# MicroMod-Teensy-Lockable.net
KiCad netlist of a schematic drawn in EAGLE
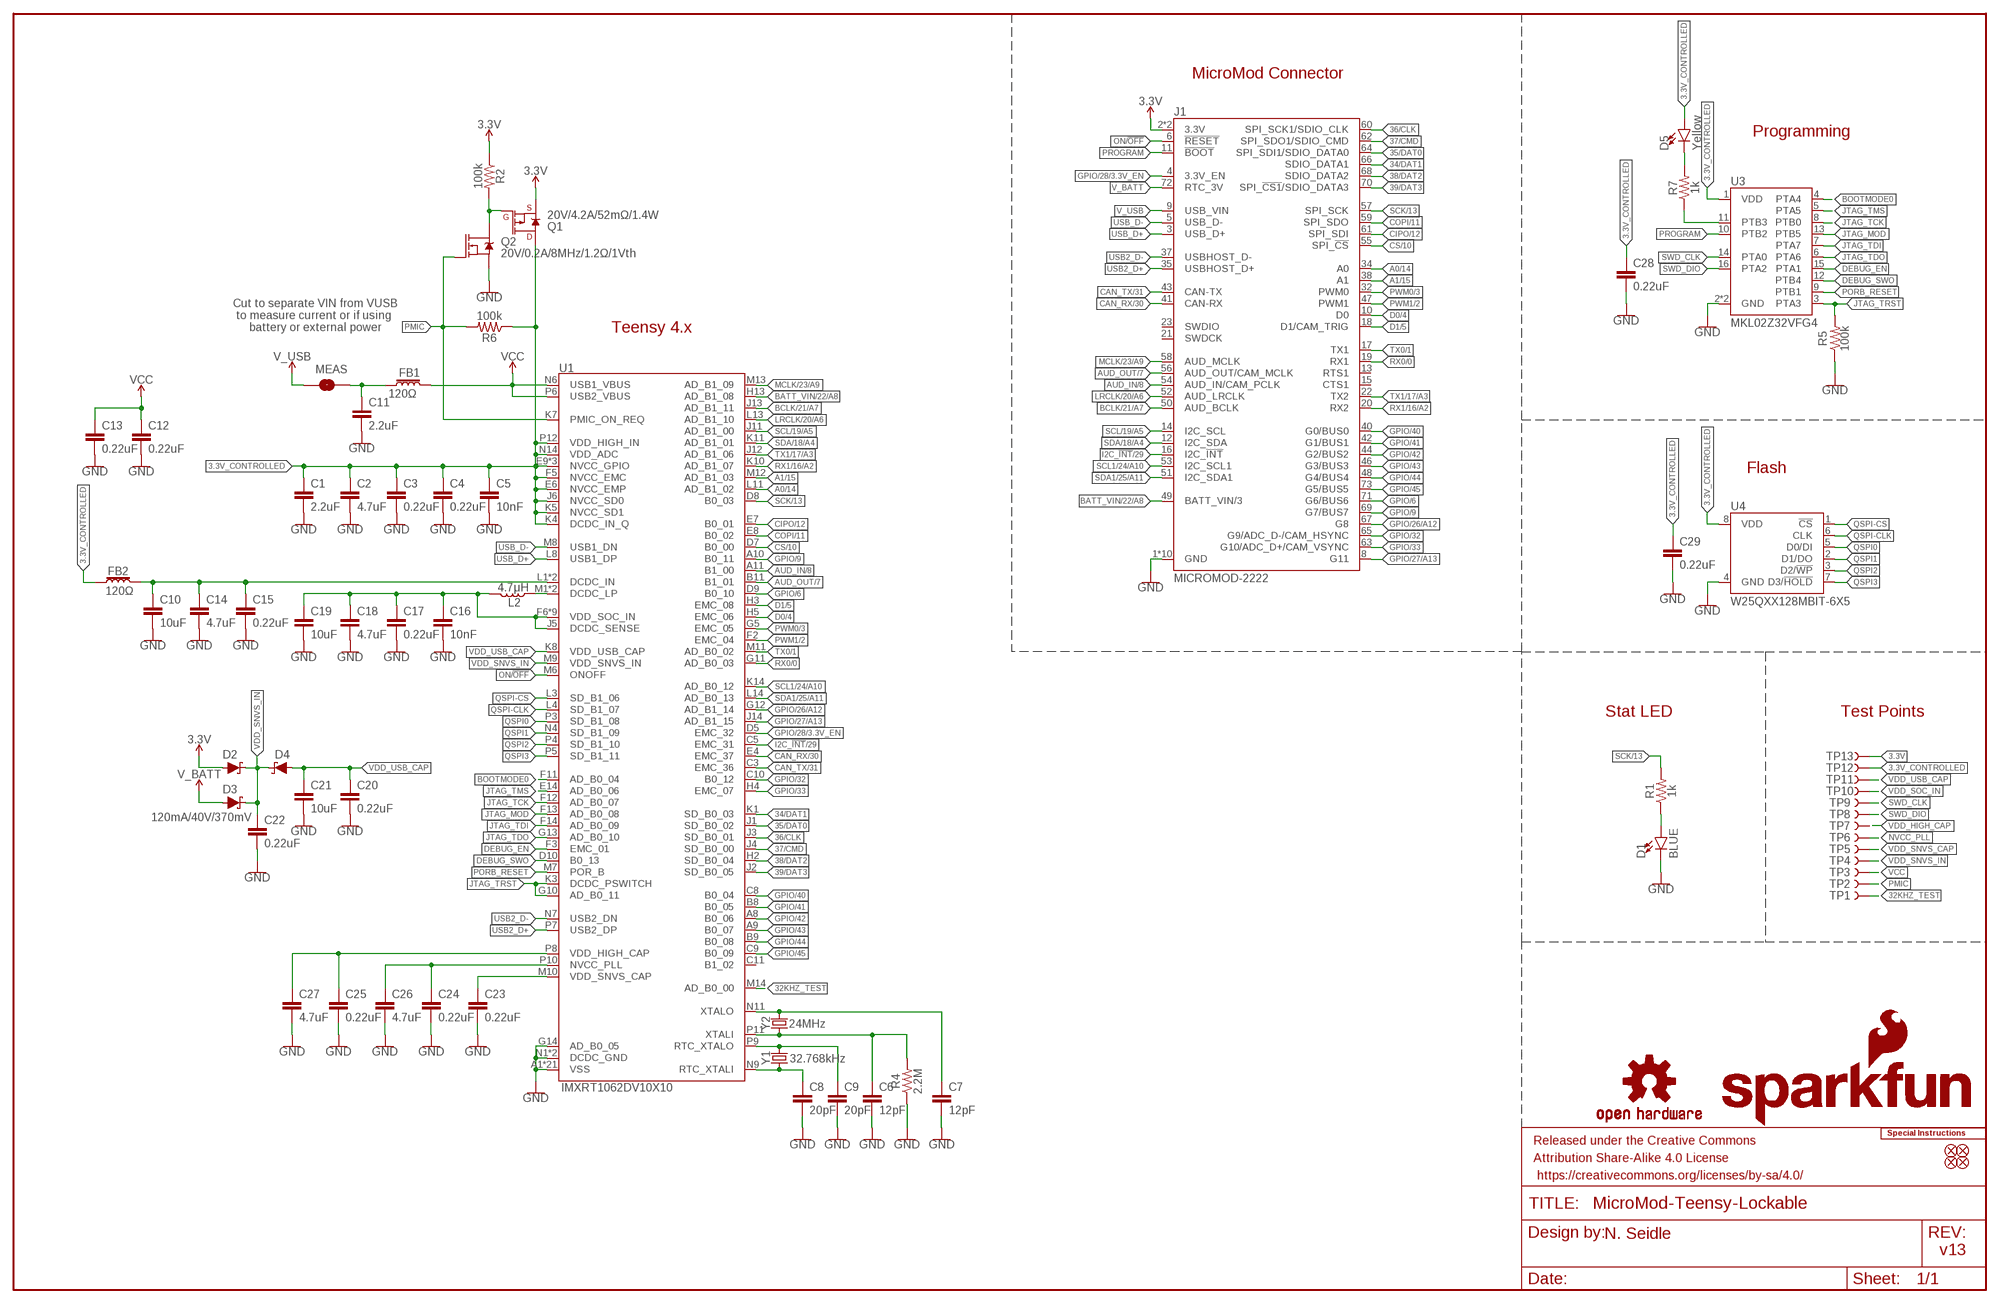
[diagram p0: schematic, sheet 1]

(export (version "E")
  (design (tool "Eeschema 10.0.6"))
  (components
    (comp (ref "C1")
      (value "2.2uF")
      (footprint "eagle-import:0402-TIGHT")
      (libsource (lib "eagle-import") (part "2.2UF-0402_TIGHT-10V-10%-X5R"))
    )
    (comp (ref "C2")
      (value "4.7uF")
      (footprint "eagle-import:0402-TIGHT")
      (libsource (lib "eagle-import") (part "4.7UF-0402_TIGHT-6.3V-20%-X5R"))
    )
    (comp (ref "C3")
      (value "0.22uF")
      (footprint "eagle-import:0402-TIGHT")
      (libsource (lib "eagle-import") (part "0.22UF-0402T-10V-10%"))
    )
    (comp (ref "C4")
      (value "0.22uF")
      (footprint "eagle-import:0402-TIGHT")
      (libsource (lib "eagle-import") (part "0.22UF-0402T-10V-10%"))
    )
    (comp (ref "C5")
      (value "10nF")
      (footprint "eagle-import:0402-TIGHT")
      (libsource (lib "eagle-import") (part "10NF-0402T-25V-10%"))
    )
    (comp (ref "C6")
      (value "12pF")
      (footprint "eagle-import:0402-TIGHT")
      (libsource (lib "eagle-import") (part "12PF-0402T-50V-5%"))
    )
    (comp (ref "C7")
      (value "12pF")
      (footprint "eagle-import:0402-TIGHT")
      (libsource (lib "eagle-import") (part "12PF-0402T-50V-5%"))
    )
    (comp (ref "C8")
      (value "20pF")
      (footprint "eagle-import:0402-TIGHT")
      (libsource (lib "eagle-import") (part "20PF-0402T-50V-5%"))
    )
    (comp (ref "C9")
      (value "20pF")
      (footprint "eagle-import:0402-TIGHT")
      (libsource (lib "eagle-import") (part "20PF-0402T-50V-5%"))
    )
    (comp (ref "C10")
      (value "10uF")
      (footprint "eagle-import:0402-TIGHT")
      (libsource (lib "eagle-import") (part "10UF-0402T-6.3V-20%"))
    )
    (comp (ref "C11")
      (value "2.2uF")
      (footprint "eagle-import:0402-TIGHT")
      (libsource (lib "eagle-import") (part "2.2UF-0402_TIGHT-10V-10%-X5R"))
    )
    (comp (ref "C12")
      (value "0.22uF")
      (footprint "eagle-import:0402-TIGHT")
      (libsource (lib "eagle-import") (part "0.22UF-0402T-10V-10%"))
    )
    (comp (ref "C13")
      (value "0.22uF")
      (footprint "eagle-import:0402-TIGHT")
      (libsource (lib "eagle-import") (part "0.22UF-0402T-10V-10%"))
    )
    (comp (ref "C14")
      (value "4.7uF")
      (footprint "eagle-import:0402-TIGHT")
      (libsource (lib "eagle-import") (part "4.7UF-0402_TIGHT-6.3V-20%-X5R"))
    )
    (comp (ref "C15")
      (value "0.22uF")
      (footprint "eagle-import:0402-TIGHT")
      (libsource (lib "eagle-import") (part "0.22UF-0402T-10V-10%"))
    )
    (comp (ref "C16")
      (value "10nF")
      (footprint "eagle-import:0402-TIGHT")
      (libsource (lib "eagle-import") (part "10NF-0402T-25V-10%"))
    )
    (comp (ref "C17")
      (value "0.22uF")
      (footprint "eagle-import:0402-TIGHT")
      (libsource (lib "eagle-import") (part "0.22UF-0402T-10V-10%"))
    )
    (comp (ref "C18")
      (value "4.7uF")
      (footprint "eagle-import:0402-TIGHT")
      (libsource (lib "eagle-import") (part "4.7UF-0402_TIGHT-6.3V-20%-X5R"))
    )
    (comp (ref "C19")
      (value "10uF")
      (footprint "eagle-import:0402-TIGHT")
      (libsource (lib "eagle-import") (part "10UF-0402T-6.3V-20%"))
    )
    (comp (ref "C20")
      (value "0.22uF")
      (footprint "eagle-import:0402-TIGHT")
      (libsource (lib "eagle-import") (part "0.22UF-0402T-10V-10%"))
    )
    (comp (ref "C21")
      (value "10uF")
      (footprint "eagle-import:0402-TIGHT")
      (libsource (lib "eagle-import") (part "10UF-0402T-6.3V-20%"))
    )
    (comp (ref "C22")
      (value "0.22uF")
      (footprint "eagle-import:0402-TIGHT")
      (libsource (lib "eagle-import") (part "0.22UF-0402T-10V-10%"))
    )
    (comp (ref "C23")
      (value "0.22uF")
      (footprint "eagle-import:0402-TIGHT")
      (libsource (lib "eagle-import") (part "0.22UF-0402T-10V-10%"))
    )
    (comp (ref "C24")
      (value "0.22uF")
      (footprint "eagle-import:0402-TIGHT")
      (libsource (lib "eagle-import") (part "0.22UF-0402T-10V-10%"))
    )
    (comp (ref "C25")
      (value "0.22uF")
      (footprint "eagle-import:0402-TIGHT")
      (libsource (lib "eagle-import") (part "0.22UF-0402T-10V-10%"))
    )
    (comp (ref "C26")
      (value "4.7uF")
      (footprint "eagle-import:0402-TIGHT")
      (libsource (lib "eagle-import") (part "4.7UF-0402_TIGHT-6.3V-20%-X5R"))
    )
    (comp (ref "C27")
      (value "4.7uF")
      (footprint "eagle-import:0402-TIGHT")
      (libsource (lib "eagle-import") (part "4.7UF-0402_TIGHT-6.3V-20%-X5R"))
    )
    (comp (ref "C28")
      (value "0.22uF")
      (footprint "eagle-import:0402-TIGHT")
      (libsource (lib "eagle-import") (part "0.22UF-0402T-10V-10%"))
    )
    (comp (ref "C29")
      (value "0.22uF")
      (footprint "eagle-import:0402-TIGHT")
      (libsource (lib "eagle-import") (part "0.22UF-0402T-10V-10%"))
    )
    (comp (ref "D1")
      (value "BLUE")
      (footprint "eagle-import:LED-0603")
      (libsource (lib "eagle-import") (part "LED-BLUE0603"))
    )
    (comp (ref "D2")
      (value "120mA/40V/370mV")
      (footprint "eagle-import:SOD-523")
      (libsource (lib "eagle-import") (part "DIODE-SCHOTTKY-RB751S40"))
    )
    (comp (ref "D3")
      (value "120mA/40V/370mV")
      (footprint "eagle-import:SOD-523")
      (libsource (lib "eagle-import") (part "DIODE-SCHOTTKY-RB751S40"))
    )
    (comp (ref "D4")
      (value "120mA/40V/370mV")
      (footprint "eagle-import:SOD-523")
      (libsource (lib "eagle-import") (part "DIODE-SCHOTTKY-RB751S40"))
    )
    (comp (ref "D5")
      (value "Yellow")
      (footprint "eagle-import:LED-0603")
      (libsource (lib "eagle-import") (part "LED-YELLOW0603"))
    )
    (comp (ref "FB1")
      (value "120Ω")
      (footprint "eagle-import:0402-TIGHT")
      (libsource (lib "eagle-import") (part "FERRITE_BEAD-120_OHM-0402T"))
    )
    (comp (ref "FB2")
      (value "120Ω")
      (footprint "eagle-import:0402-TIGHT")
      (libsource (lib "eagle-import") (part "FERRITE_BEAD-120_OHM-0402T"))
    )
    (comp (ref "FD1")
      (value "FIDUCIALUFIDUCIAL")
      (footprint "eagle-import:FIDUCIAL-MICRO")
      (libsource (lib "eagle-import") (part "FIDUCIALUFIDUCIAL"))
    )
    (comp (ref "FD2")
      (value "FIDUCIALUFIDUCIAL")
      (footprint "eagle-import:FIDUCIAL-MICRO")
      (libsource (lib "eagle-import") (part "FIDUCIALUFIDUCIAL"))
    )
    (comp (ref "FD3")
      (value "FIDUCIALUFIDUCIAL")
      (footprint "eagle-import:FIDUCIAL-MICRO")
      (libsource (lib "eagle-import") (part "FIDUCIALUFIDUCIAL"))
    )
    (comp (ref "FD4")
      (value "FIDUCIALUFIDUCIAL")
      (footprint "eagle-import:FIDUCIAL-MICRO")
      (libsource (lib "eagle-import") (part "FIDUCIALUFIDUCIAL"))
    )
    (comp (ref "FRAME1")
      (value "FRAME-LEDGER")
      (footprint "eagle-import:CREATIVE_COMMONS")
      (libsource (lib "eagle-import") (part "FRAME-LEDGER"))
    )
    (comp (ref "J1")
      (value "MICROMOD-2222")
      (footprint "eagle-import:M.2-CARD-E-22")
      (libsource (lib "eagle-import") (part "MICROMOD-2222"))
    )
    (comp (ref "L2")
      (value "4.7μH")
      (footprint "eagle-import:1008(2520)")
      (libsource (lib "eagle-import") (part "4.7μH_SHIELDED_INDUCTOR"))
    )
    (comp (ref "LOGO1")
      (value "SFE_LOGO_NAME_FLAME.1_INCH")
      (footprint "eagle-import:SFE_LOGO_NAME_FLAME_.1")
      (libsource (lib "eagle-import") (part "SFE_LOGO_NAME_FLAME.1_INCH"))
    )
    (comp (ref "LOGO2")
      (value "OSHW-LOGONO_SILK")
      (footprint "eagle-import:DUMMY")
      (libsource (lib "eagle-import") (part "OSHW-LOGONO_SILK"))
    )
    (comp (ref "LOGO3")
      (value "SPECIAL_INSTRUCTIONS-ORDERING")
      (footprint "eagle-import:ORDERING_INSTRUCTIONS")
      (libsource (lib "eagle-import") (part "SPECIAL_INSTRUCTIONS-ORDERING"))
    )
    (comp (ref "MEAS")
      (value "JUMPER-SMT_2_NC_TRACE_SILK")
      (footprint "eagle-import:SMT-JUMPER_2_NC_TRACE_SILK")
      (libsource (lib "eagle-import") (part "JUMPER-SMT_2_NC_TRACE_SILK"))
    )
    (comp (ref "Q1")
      (value "20V/4.2A/52mΩ/1.4W")
      (footprint "eagle-import:SOT23-3")
      (libsource (lib "eagle-import") (part "MOSFET_PCH-DMG2305UX-7"))
    )
    (comp (ref "Q2")
      (value "20V/0.2A/8MHz/1.2Ω/1Vth")
      (footprint "eagle-import:SOT-416FL")
      (libsource (lib "eagle-import") (part "MOSFET-NCH-RE1C00UNTL"))
    )
    (comp (ref "R1")
      (value "1k")
      (footprint "eagle-import:0402-TIGHT")
      (libsource (lib "eagle-import") (part "1KOHM-0402T-1/16W-1%"))
    )
    (comp (ref "R2")
      (value "100k")
      (footprint "eagle-import:0402-TIGHT")
      (libsource (lib "eagle-import") (part "100KOHM-0402T-1/16W-1%"))
    )
    (comp (ref "R4")
      (value "2.2M")
      (footprint "eagle-import:0402-TIGHT")
      (libsource (lib "eagle-import") (part "2.2MOHMS-0402T-1/10W-1%"))
    )
    (comp (ref "R5")
      (value "100k")
      (footprint "eagle-import:0402-TIGHT")
      (libsource (lib "eagle-import") (part "100KOHM-0402T-1/16W-1%"))
    )
    (comp (ref "R6")
      (value "100k")
      (footprint "eagle-import:0402-TIGHT")
      (libsource (lib "eagle-import") (part "100KOHM-0402T-1/16W-1%"))
    )
    (comp (ref "R7")
      (value "1k")
      (footprint "eagle-import:0402-TIGHT")
      (libsource (lib "eagle-import") (part "1KOHM-0402T-1/16W-1%"))
    )
    (comp (ref "TP1")
      (value "TEST-POINT3")
      (footprint "eagle-import:PAD.03X.03")
      (libsource (lib "eagle-import") (part "TEST-POINT3"))
    )
    (comp (ref "TP2")
      (value "TEST-POINT3")
      (footprint "eagle-import:PAD.03X.03")
      (libsource (lib "eagle-import") (part "TEST-POINT3"))
    )
    (comp (ref "TP3")
      (value "TEST-POINT3")
      (footprint "eagle-import:PAD.03X.03")
      (libsource (lib "eagle-import") (part "TEST-POINT3"))
    )
    (comp (ref "TP4")
      (value "TEST-POINT3")
      (footprint "eagle-import:PAD.03X.03")
      (libsource (lib "eagle-import") (part "TEST-POINT3"))
    )
    (comp (ref "TP5")
      (value "TEST-POINT3")
      (footprint "eagle-import:PAD.03X.03")
      (libsource (lib "eagle-import") (part "TEST-POINT3"))
    )
    (comp (ref "TP6")
      (value "TEST-POINT3")
      (footprint "eagle-import:PAD.03X.03")
      (libsource (lib "eagle-import") (part "TEST-POINT3"))
    )
    (comp (ref "TP7")
      (value "TEST-POINT3")
      (footprint "eagle-import:PAD.03X.03")
      (libsource (lib "eagle-import") (part "TEST-POINT3"))
    )
    (comp (ref "TP8")
      (value "TEST-POINT3")
      (footprint "eagle-import:PAD.03X.03")
      (libsource (lib "eagle-import") (part "TEST-POINT3"))
    )
    (comp (ref "TP9")
      (value "TEST-POINT3")
      (footprint "eagle-import:PAD.03X.03")
      (libsource (lib "eagle-import") (part "TEST-POINT3"))
    )
    (comp (ref "TP10")
      (value "TEST-POINT3")
      (footprint "eagle-import:PAD.03X.03")
      (libsource (lib "eagle-import") (part "TEST-POINT3"))
    )
    (comp (ref "TP11")
      (value "TEST-POINT3")
      (footprint "eagle-import:PAD.03X.03")
      (libsource (lib "eagle-import") (part "TEST-POINT3"))
    )
    (comp (ref "TP12")
      (value "TEST-POINT3")
      (footprint "eagle-import:PAD.03X.03")
      (libsource (lib "eagle-import") (part "TEST-POINT3"))
    )
    (comp (ref "TP13")
      (value "TEST-POINT3")
      (footprint "eagle-import:PAD.03X.03")
      (libsource (lib "eagle-import") (part "TEST-POINT3"))
    )
    (comp (ref "U1")
      (value "IMXRT1062DV10X10")
      (footprint "eagle-import:IMXRT1062")
      (libsource (lib "eagle-import") (part "IMXRT1062DV10X10"))
    )
    (comp (ref "U3")
      (value "MKL02Z32VFG4")
      (footprint "eagle-import:QFN-16")
      (libsource (lib "eagle-import") (part "MKL02Z32VFG4QFN-16"))
    )
    (comp (ref "U4")
      (value "W25QXX128MBIT-6X5")
      (footprint "eagle-import:WSON-8-6X5-SKINNY_CENTERPAD")
      (libsource (lib "eagle-import") (part "W25QXX128MBIT-6X5-SKINNY_CENTER"))
    )
    (comp (ref "Y1")
      (value "32.768kHz")
      (footprint "eagle-import:CRYSTAL-SMD-3.2X1.5MM")
      (libsource (lib "eagle-import") (part "CRYSTAL-32.768KHZSMD-3.2X1.5"))
    )
    (comp (ref "Y2")
      (value "24MHz")
      (footprint "eagle-import:CRYSTAL-SMD-2.0X1.6MM")
      (libsource (lib "eagle-import") (part "CRYSTAL-24MHZ-SMD-2.0X1.6MM"))
    )
  )
  (nets
    (net (code "1") (name "/I2C_~{INT}{slash}29") (class "Default")
      (node (ref "J1") (pin "16") (pinfunction "I2C_~{INT}_16") (pintype "bidirectional"))
      (node (ref "U1") (pin "C5") (pinfunction "EMC_31_C5") (pintype "bidirectional"))
    )
    (net (code "2") (name "/ON{slash}~{OFF}") (class "Default")
      (node (ref "J1") (pin "6") (pinfunction "~{RESET}_6") (pintype "bidirectional"))
      (node (ref "U1") (pin "M6") (pinfunction "ONOFF_M6") (pintype "bidirectional"))
    )
    (net (code "3") (name "3.3V") (class "Default")
      (node (ref "D2") (pin "A") (pinfunction "A_A") (pintype "passive"))
      (node (ref "J1") (pin "2") (pinfunction "3.3V_2") (pintype "bidirectional"))
      (node (ref "J1") (pin "74") (pinfunction "3.3V_74") (pintype "bidirectional"))
      (node (ref "Q1") (pin "2") (pinfunction "S_2") (pintype "bidirectional"))
      (node (ref "R2") (pin "1") (pinfunction "1_1") (pintype "passive"))
      (node (ref "TP13") (pin "P$1") (pinfunction "1_P$1") (pintype "bidirectional"))
    )
    (net (code "4") (name "3.3V_CONTROLLED") (class "Default")
      (node (ref "C1") (pin "1") (pinfunction "1_1") (pintype "passive"))
      (node (ref "C2") (pin "1") (pinfunction "1_1") (pintype "passive"))
      (node (ref "C28") (pin "1") (pinfunction "1_1") (pintype "passive"))
      (node (ref "C29") (pin "1") (pinfunction "1_1") (pintype "passive"))
      (node (ref "C3") (pin "1") (pinfunction "1_1") (pintype "passive"))
      (node (ref "C4") (pin "1") (pinfunction "1_1") (pintype "passive"))
      (node (ref "C5") (pin "1") (pinfunction "1_1") (pintype "passive"))
      (node (ref "D5") (pin "A") (pinfunction "A_A") (pintype "passive"))
      (node (ref "FB2") (pin "1") (pinfunction "1_1") (pintype "passive"))
      (node (ref "Q1") (pin "3") (pinfunction "D_3") (pintype "bidirectional"))
      (node (ref "R6") (pin "1") (pinfunction "1_1") (pintype "passive"))
      (node (ref "TP12") (pin "P$1") (pinfunction "1_P$1") (pintype "bidirectional"))
      (node (ref "U1") (pin "E6") (pinfunction "NVCC_EMP_E6") (pintype "bidirectional"))
      (node (ref "U1") (pin "E9") (pinfunction "NVCC_GPIO_E9") (pintype "bidirectional"))
      (node (ref "U1") (pin "F10") (pinfunction "NVCC_GPIO_F10") (pintype "bidirectional"))
      (node (ref "U1") (pin "F5") (pinfunction "NVCC_EMC_F5") (pintype "bidirectional"))
      (node (ref "U1") (pin "J10") (pinfunction "NVCC_GPIO_J10") (pintype "bidirectional"))
      (node (ref "U1") (pin "J6") (pinfunction "NVCC_SD0_J6") (pintype "bidirectional"))
      (node (ref "U1") (pin "K4") (pinfunction "DCDC_IN_Q_K4") (pintype "bidirectional"))
      (node (ref "U1") (pin "K5") (pinfunction "NVCC_SD1_K5") (pintype "bidirectional"))
      (node (ref "U1") (pin "N14") (pinfunction "VDD_ADC_N14") (pintype "bidirectional"))
      (node (ref "U1") (pin "P12") (pinfunction "VDD_HIGH_IN_P12") (pintype "bidirectional"))
      (node (ref "U3") (pin "1") (pinfunction "VDD_1") (pintype "bidirectional"))
      (node (ref "U4") (pin "8") (pinfunction "VDD_8") (pintype "bidirectional"))
    )
    (net (code "5") (name "32KHZ_TEST") (class "Default")
      (node (ref "TP1") (pin "P$1") (pinfunction "1_P$1") (pintype "bidirectional"))
      (node (ref "U1") (pin "M14") (pinfunction "AD_B0_00_M14") (pintype "bidirectional"))
    )
    (net (code "6") (name "34{slash}DAT1") (class "Default")
      (node (ref "J1") (pin "66") (pinfunction "SDIO_DATA1_66") (pintype "bidirectional"))
      (node (ref "U1") (pin "K1") (pinfunction "SD_B0_03_K1") (pintype "bidirectional"))
    )
    (net (code "7") (name "35{slash}DAT0") (class "Default")
      (node (ref "J1") (pin "64") (pinfunction "SPI_SDI1/SDIO_DATA0_64") (pintype "bidirectional"))
      (node (ref "U1") (pin "J1") (pinfunction "SD_B0_02_J1") (pintype "bidirectional"))
    )
    (net (code "8") (name "36{slash}CLK") (class "Default")
      (node (ref "J1") (pin "60") (pinfunction "SPI_SCK1/SDIO_CLK_60") (pintype "bidirectional"))
      (node (ref "U1") (pin "J3") (pinfunction "SD_B0_01_J3") (pintype "bidirectional"))
    )
    (net (code "9") (name "37{slash}CMD") (class "Default")
      (node (ref "J1") (pin "62") (pinfunction "SPI_SDO1/SDIO_CMD_62") (pintype "bidirectional"))
      (node (ref "U1") (pin "J4") (pinfunction "SD_B0_00_J4") (pintype "bidirectional"))
    )
    (net (code "10") (name "38{slash}DAT2") (class "Default")
      (node (ref "J1") (pin "68") (pinfunction "SDIO_DATA2_68") (pintype "bidirectional"))
      (node (ref "U1") (pin "H2") (pinfunction "SD_B0_04_H2") (pintype "bidirectional"))
    )
    (net (code "11") (name "39{slash}DAT3") (class "Default")
      (node (ref "J1") (pin "70") (pinfunction "SPI_~{CS1}/SDIO_DATA3_70") (pintype "bidirectional"))
      (node (ref "U1") (pin "J2") (pinfunction "SD_B0_05_J2") (pintype "bidirectional"))
    )
    (net (code "12") (name "A0{slash}14") (class "Default")
      (node (ref "J1") (pin "34") (pinfunction "A0_34") (pintype "bidirectional"))
      (node (ref "U1") (pin "L11") (pinfunction "AD_B1_02_L11") (pintype "bidirectional"))
    )
    (net (code "13") (name "A1{slash}15") (class "Default")
      (node (ref "J1") (pin "38") (pinfunction "A1_38") (pintype "bidirectional"))
      (node (ref "U1") (pin "M12") (pinfunction "AD_B1_03_M12") (pintype "bidirectional"))
    )
    (net (code "14") (name "AUD_IN{slash}8") (class "Default")
      (node (ref "J1") (pin "54") (pinfunction "AUD_IN/CAM_PCLK_54") (pintype "bidirectional"))
      (node (ref "U1") (pin "A11") (pinfunction "B1_00_A11") (pintype "bidirectional"))
    )
    (net (code "15") (name "AUD_OUT{slash}7") (class "Default")
      (node (ref "J1") (pin "56") (pinfunction "AUD_OUT/CAM_MCLK_56") (pintype "bidirectional"))
      (node (ref "U1") (pin "B11") (pinfunction "B1_01_B11") (pintype "bidirectional"))
    )
    (net (code "16") (name "BATT_VIN{slash}22{slash}A8") (class "Default")
      (node (ref "J1") (pin "49") (pinfunction "BATT_VIN/3_49") (pintype "bidirectional"))
      (node (ref "U1") (pin "H13") (pinfunction "AD_B1_08_H13") (pintype "bidirectional"))
    )
    (net (code "17") (name "BCLK{slash}21{slash}A7") (class "Default")
      (node (ref "J1") (pin "50") (pinfunction "AUD_BCLK_50") (pintype "bidirectional"))
      (node (ref "U1") (pin "J13") (pinfunction "AD_B1_11_J13") (pintype "bidirectional"))
    )
    (net (code "18") (name "BOOTMODE0") (class "Default")
      (node (ref "U1") (pin "F11") (pinfunction "AD_B0_04_F11") (pintype "bidirectional"))
      (node (ref "U3") (pin "4") (pinfunction "PTA4_4") (pintype "bidirectional"))
    )
    (net (code "19") (name "CAN_RX{slash}30") (class "Default")
      (node (ref "J1") (pin "41") (pinfunction "CAN-RX_41") (pintype "bidirectional"))
      (node (ref "U1") (pin "E4") (pinfunction "EMC_37_E4") (pintype "bidirectional"))
    )
    (net (code "20") (name "CAN_TX{slash}31") (class "Default")
      (node (ref "J1") (pin "43") (pinfunction "CAN-TX_43") (pintype "bidirectional"))
      (node (ref "U1") (pin "C3") (pinfunction "EMC_36_C3") (pintype "bidirectional"))
    )
    (net (code "21") (name "CIPO{slash}12") (class "Default")
      (node (ref "J1") (pin "61") (pinfunction "SPI_SDI_61") (pintype "bidirectional"))
      (node (ref "U1") (pin "E7") (pinfunction "B0_01_E7") (pintype "bidirectional"))
    )
    (net (code "22") (name "COPI{slash}11") (class "Default")
      (node (ref "J1") (pin "59") (pinfunction "SPI_SDO_59") (pintype "bidirectional"))
      (node (ref "U1") (pin "E8") (pinfunction "B0_02_E8") (pintype "bidirectional"))
    )
    (net (code "23") (name "CS{slash}10") (class "Default")
      (node (ref "J1") (pin "55") (pinfunction "SPI_~{CS}_55") (pintype "bidirectional"))
      (node (ref "U1") (pin "D7") (pinfunction "B0_00_D7") (pintype "bidirectional"))
    )
    (net (code "24") (name "D0{slash}4") (class "Default")
      (node (ref "J1") (pin "10") (pinfunction "D0_10") (pintype "bidirectional"))
      (node (ref "U1") (pin "H5") (pinfunction "EMC_06_H5") (pintype "bidirectional"))
    )
    (net (code "25") (name "D1{slash}5") (class "Default")
      (node (ref "J1") (pin "18") (pinfunction "D1/CAM_TRIG_18") (pintype "bidirectional"))
      (node (ref "U1") (pin "H3") (pinfunction "EMC_08_H3") (pintype "bidirectional"))
    )
    (net (code "26") (name "DEBUG_EN") (class "Default")
      (node (ref "U1") (pin "F3") (pinfunction "EMC_01_F3") (pintype "bidirectional"))
      (node (ref "U3") (pin "15") (pinfunction "PTA1_15") (pintype "bidirectional"))
    )
    (net (code "27") (name "DEBUG_SWO") (class "Default")
      (node (ref "U1") (pin "D10") (pinfunction "B0_13_D10") (pintype "bidirectional"))
      (node (ref "U3") (pin "12") (pinfunction "PTB4_12") (pintype "bidirectional"))
    )
    (net (code "28") (name "GND") (class "Default")
      (node (ref "C1") (pin "2") (pinfunction "2_2") (pintype "passive"))
      (node (ref "C10") (pin "2") (pinfunction "2_2") (pintype "passive"))
      (node (ref "C11") (pin "2") (pinfunction "2_2") (pintype "passive"))
      (node (ref "C12") (pin "2") (pinfunction "2_2") (pintype "passive"))
      (node (ref "C13") (pin "2") (pinfunction "2_2") (pintype "passive"))
      (node (ref "C14") (pin "2") (pinfunction "2_2") (pintype "passive"))
      (node (ref "C15") (pin "2") (pinfunction "2_2") (pintype "passive"))
      (node (ref "C16") (pin "2") (pinfunction "2_2") (pintype "passive"))
      (node (ref "C17") (pin "2") (pinfunction "2_2") (pintype "passive"))
      (node (ref "C18") (pin "2") (pinfunction "2_2") (pintype "passive"))
      (node (ref "C19") (pin "2") (pinfunction "2_2") (pintype "passive"))
      (node (ref "C2") (pin "2") (pinfunction "2_2") (pintype "passive"))
      (node (ref "C20") (pin "2") (pinfunction "2_2") (pintype "passive"))
      (node (ref "C21") (pin "2") (pinfunction "2_2") (pintype "passive"))
      (node (ref "C22") (pin "2") (pinfunction "2_2") (pintype "passive"))
      (node (ref "C23") (pin "2") (pinfunction "2_2") (pintype "passive"))
      (node (ref "C24") (pin "2") (pinfunction "2_2") (pintype "passive"))
      (node (ref "C25") (pin "2") (pinfunction "2_2") (pintype "passive"))
      (node (ref "C26") (pin "2") (pinfunction "2_2") (pintype "passive"))
      (node (ref "C27") (pin "2") (pinfunction "2_2") (pintype "passive"))
      (node (ref "C28") (pin "2") (pinfunction "2_2") (pintype "passive"))
      (node (ref "C29") (pin "2") (pinfunction "2_2") (pintype "passive"))
      (node (ref "C3") (pin "2") (pinfunction "2_2") (pintype "passive"))
      (node (ref "C4") (pin "2") (pinfunction "2_2") (pintype "passive"))
      (node (ref "C5") (pin "2") (pinfunction "2_2") (pintype "passive"))
      (node (ref "C6") (pin "2") (pinfunction "2_2") (pintype "passive"))
      (node (ref "C7") (pin "2") (pinfunction "2_2") (pintype "passive"))
      (node (ref "C8") (pin "2") (pinfunction "2_2") (pintype "passive"))
      (node (ref "C9") (pin "2") (pinfunction "2_2") (pintype "passive"))
      (node (ref "D1") (pin "C") (pinfunction "C_C") (pintype "passive"))
      (node (ref "J1") (pin "1") (pinfunction "GND_1") (pintype "bidirectional"))
      (node (ref "J1") (pin "33") (pinfunction "GND_33") (pintype "bidirectional"))
      (node (ref "J1") (pin "36") (pinfunction "GND_36") (pintype "bidirectional"))
      (node (ref "J1") (pin "39") (pinfunction "GND_39") (pintype "bidirectional"))
      (node (ref "J1") (pin "45") (pinfunction "GND_45") (pintype "bidirectional"))
      (node (ref "J1") (pin "7") (pinfunction "GND_7") (pintype "bidirectional"))
      (node (ref "J1") (pin "75") (pinfunction "GND_75") (pintype "bidirectional"))
      (node (ref "J1") (pin "GND1") (pinfunction "GND_GND1") (pintype "bidirectional"))
      (node (ref "J1") (pin "GND2") (pinfunction "GND_GND2") (pintype "bidirectional"))
      (node (ref "J1") (pin "GND3") (pinfunction "GND_GND3") (pintype "bidirectional"))
      (node (ref "Q2") (pin "2") (pinfunction "S_2") (pintype "bidirectional"))
      (node (ref "R4") (pin "1") (pinfunction "1_1") (pintype "passive"))
      (node (ref "R5") (pin "1") (pinfunction "1_1") (pintype "passive"))
      (node (ref "U1") (pin "A1") (pinfunction "VSS_A1") (pintype "bidirectional"))
      (node (ref "U1") (pin "A14") (pinfunction "VSS_A14") (pintype "bidirectional"))
      (node (ref "U1") (pin "B10") (pinfunction "VSS_B10") (pintype "bidirectional"))
      (node (ref "U1") (pin "B5") (pinfunction "VSS_B5") (pintype "bidirectional"))
      (node (ref "U1") (pin "E13") (pinfunction "VSS_E13") (pintype "bidirectional"))
      (node (ref "U1") (pin "E2") (pinfunction "VSS_E2") (pintype "bidirectional"))
      (node (ref "U1") (pin "G14") (pinfunction "AD_B0_05_G14") (pintype "bidirectional"))
      (node (ref "U1") (pin "G7") (pinfunction "VSS_G7") (pintype "bidirectional"))
      (node (ref "U1") (pin "G8") (pinfunction "VSS_G8") (pintype "bidirectional"))
      (node (ref "U1") (pin "H7") (pinfunction "VSS_H7") (pintype "bidirectional"))
      (node (ref "U1") (pin "H8") (pinfunction "VSS_H8") (pintype "bidirectional"))
      (node (ref "U1") (pin "J7") (pinfunction "VSS_J7") (pintype "bidirectional"))
      (node (ref "U1") (pin "J8") (pinfunction "VSS_J8") (pintype "bidirectional"))
      (node (ref "U1") (pin "K13") (pinfunction "VSS_K13") (pintype "bidirectional"))
      (node (ref "U1") (pin "K2") (pinfunction "VSS_K2") (pintype "bidirectional"))
      (node (ref "U1") (pin "K6") (pinfunction "VSS_K6") (pintype "bidirectional"))
      (node (ref "U1") (pin "K9") (pinfunction "VSS_K9") (pintype "bidirectional"))
      (node (ref "U1") (pin "L9") (pinfunction "VSS_L9") (pintype "bidirectional"))
      (node (ref "U1") (pin "N1") (pinfunction "DCDC_GND_N1") (pintype "bidirectional"))
      (node (ref "U1") (pin "N2") (pinfunction "DCDC_GND_N2") (pintype "bidirectional"))
      (node (ref "U1") (pin "N5") (pinfunction "VSS_N5") (pintype "bidirectional"))
      (node (ref "U1") (pin "N8") (pinfunction "VSS_N8") (pintype "bidirectional"))
      (node (ref "U1") (pin "P1") (pinfunction "VSS_P1") (pintype "bidirectional"))
      (node (ref "U1") (pin "P14") (pinfunction "VSS_P14") (pintype "bidirectional"))
      (node (ref "U3") (pin "17") (pinfunction "GND_17") (pintype "bidirectional"))
      (node (ref "U3") (pin "2") (pinfunction "GND_2") (pintype "bidirectional"))
      (node (ref "U4") (pin "4") (pinfunction "GND_4") (pintype "bidirectional"))
    )
    (net (code "29") (name "GPIO{slash}6") (class "Default")
      (node (ref "J1") (pin "71") (pinfunction "G6/BUS6_71") (pintype "bidirectional"))
      (node (ref "U1") (pin "D9") (pinfunction "B0_10_D9") (pintype "bidirectional"))
    )
    (net (code "30") (name "GPIO{slash}9") (class "Default")
      (node (ref "J1") (pin "69") (pinfunction "G7/BUS7_69") (pintype "bidirectional"))
      (node (ref "U1") (pin "A10") (pinfunction "B0_11_A10") (pintype "bidirectional"))
    )
    (net (code "31") (name "GPIO{slash}26{slash}A12") (class "Default")
      (node (ref "J1") (pin "67") (pinfunction "G8_67") (pintype "bidirectional"))
      (node (ref "U1") (pin "G12") (pinfunction "AD_B1_14_G12") (pintype "bidirectional"))
    )
    (net (code "32") (name "GPIO{slash}27{slash}A13") (class "Default")
      (node (ref "J1") (pin "8") (pinfunction "G11_8") (pintype "bidirectional"))
      (node (ref "U1") (pin "J14") (pinfunction "AD_B1_15_J14") (pintype "bidirectional"))
    )
    (net (code "33") (name "GPIO{slash}28{slash}3.3V_EN") (class "Default")
      (node (ref "J1") (pin "4") (pinfunction "3.3V_EN_4") (pintype "bidirectional"))
      (node (ref "U1") (pin "D5") (pinfunction "EMC_32_D5") (pintype "bidirectional"))
    )
    (net (code "34") (name "GPIO{slash}32") (class "Default")
      (node (ref "J1") (pin "65") (pinfunction "G9/ADC_D-/CAM_HSYNC_65") (pintype "bidirectional"))
      (node (ref "U1") (pin "C10") (pinfunction "B0_12_C10") (pintype "bidirectional"))
    )
    (net (code "35") (name "GPIO{slash}33") (class "Default")
      (node (ref "J1") (pin "63") (pinfunction "G10/ADC_D+/CAM_VSYNC_63") (pintype "bidirectional"))
      (node (ref "U1") (pin "H4") (pinfunction "EMC_07_H4") (pintype "bidirectional"))
    )
    (net (code "36") (name "GPIO{slash}40") (class "Default")
      (node (ref "J1") (pin "40") (pinfunction "G0/BUS0_40") (pintype "bidirectional"))
      (node (ref "U1") (pin "C8") (pinfunction "B0_04_C8") (pintype "bidirectional"))
    )
    (net (code "37") (name "GPIO{slash}41") (class "Default")
      (node (ref "J1") (pin "42") (pinfunction "G1/BUS1_42") (pintype "bidirectional"))
      (node (ref "U1") (pin "B8") (pinfunction "B0_05_B8") (pintype "bidirectional"))
    )
    (net (code "38") (name "GPIO{slash}42") (class "Default")
      (node (ref "J1") (pin "44") (pinfunction "G2/BUS2_44") (pintype "bidirectional"))
      (node (ref "U1") (pin "A8") (pinfunction "B0_06_A8") (pintype "bidirectional"))
    )
    (net (code "39") (name "GPIO{slash}43") (class "Default")
      (node (ref "J1") (pin "46") (pinfunction "G3/BUS3_46") (pintype "bidirectional"))
      (node (ref "U1") (pin "A9") (pinfunction "B0_07_A9") (pintype "bidirectional"))
    )
    (net (code "40") (name "GPIO{slash}44") (class "Default")
      (node (ref "J1") (pin "48") (pinfunction "G4/BUS4_48") (pintype "bidirectional"))
      (node (ref "U1") (pin "B9") (pinfunction "B0_08_B9") (pintype "bidirectional"))
    )
    (net (code "41") (name "GPIO{slash}45") (class "Default")
      (node (ref "J1") (pin "73") (pinfunction "G5/BUS5_73") (pintype "bidirectional"))
      (node (ref "U1") (pin "C9") (pinfunction "B0_09_C9") (pintype "bidirectional"))
    )
    (net (code "42") (name "JTAG_MOD") (class "Default")
      (node (ref "U1") (pin "F13") (pinfunction "AD_B0_08_F13") (pintype "bidirectional"))
      (node (ref "U3") (pin "13") (pinfunction "PTB5_13") (pintype "bidirectional"))
    )
    (net (code "43") (name "JTAG_TCK") (class "Default")
      (node (ref "U1") (pin "F12") (pinfunction "AD_B0_07_F12") (pintype "bidirectional"))
      (node (ref "U3") (pin "8") (pinfunction "PTB0_8") (pintype "bidirectional"))
    )
    (net (code "44") (name "JTAG_TDI") (class "Default")
      (node (ref "U1") (pin "F14") (pinfunction "AD_B0_09_F14") (pintype "bidirectional"))
      (node (ref "U3") (pin "7") (pinfunction "PTA7_7") (pintype "bidirectional"))
    )
    (net (code "45") (name "JTAG_TDO") (class "Default")
      (node (ref "U1") (pin "G13") (pinfunction "AD_B0_10_G13") (pintype "bidirectional"))
      (node (ref "U3") (pin "6") (pinfunction "PTA6_6") (pintype "bidirectional"))
    )
    (net (code "46") (name "JTAG_TMS") (class "Default")
      (node (ref "U1") (pin "E14") (pinfunction "AD_B0_06_E14") (pintype "bidirectional"))
      (node (ref "U3") (pin "5") (pinfunction "PTA5_5") (pintype "bidirectional"))
    )
    (net (code "47") (name "JTAG_TRST") (class "Default")
      (node (ref "R5") (pin "2") (pinfunction "2_2") (pintype "passive"))
      (node (ref "U1") (pin "G10") (pinfunction "AD_B0_11_G10") (pintype "bidirectional"))
      (node (ref "U1") (pin "K3") (pinfunction "DCDC_PSWITCH_K3") (pintype "bidirectional"))
      (node (ref "U3") (pin "3") (pinfunction "PTA3_3") (pintype "bidirectional"))
    )
    (net (code "48") (name "LRCLK{slash}20{slash}A6") (class "Default")
      (node (ref "J1") (pin "52") (pinfunction "AUD_LRCLK_52") (pintype "bidirectional"))
      (node (ref "U1") (pin "L13") (pinfunction "AD_B1_10_L13") (pintype "bidirectional"))
    )
    (net (code "49") (name "MCLK{slash}23{slash}A9") (class "Default")
      (node (ref "J1") (pin "58") (pinfunction "AUD_MCLK_58") (pintype "bidirectional"))
      (node (ref "U1") (pin "M13") (pinfunction "AD_B1_09_M13") (pintype "bidirectional"))
    )
    (net (code "50") (name "NVCC_PLL") (class "Default")
      (node (ref "C24") (pin "1") (pinfunction "1_1") (pintype "passive"))
      (node (ref "C26") (pin "1") (pinfunction "1_1") (pintype "passive"))
      (node (ref "TP6") (pin "P$1") (pinfunction "1_P$1") (pintype "bidirectional"))
      (node (ref "U1") (pin "P10") (pinfunction "NVCC_PLL_P10") (pintype "bidirectional"))
    )
    (net (code "51") (name "Net-(C10-Pad1)") (class "Default")
      (node (ref "C10") (pin "1") (pinfunction "1_1") (pintype "passive"))
      (node (ref "C14") (pin "1") (pinfunction "1_1") (pintype "passive"))
      (node (ref "C15") (pin "1") (pinfunction "1_1") (pintype "passive"))
      (node (ref "FB2") (pin "2") (pinfunction "2_2") (pintype "passive"))
      (node (ref "U1") (pin "L1") (pinfunction "DCDC_IN_L1") (pintype "bidirectional"))
      (node (ref "U1") (pin "L2") (pinfunction "DCDC_IN_L2") (pintype "bidirectional"))
    )
    (net (code "52") (name "Net-(C11-Pad1)") (class "Default")
      (node (ref "C11") (pin "1") (pinfunction "1_1") (pintype "passive"))
      (node (ref "FB1") (pin "1") (pinfunction "1_1") (pintype "passive"))
      (node (ref "MEAS") (pin "2") (pinfunction "2_2") (pintype "passive"))
    )
    (net (code "53") (name "Net-(D1-PadA)") (class "Default")
      (node (ref "D1") (pin "A") (pinfunction "A_A") (pintype "passive"))
      (node (ref "R1") (pin "1") (pinfunction "1_1") (pintype "passive"))
    )
    (net (code "54") (name "Net-(D5-PadC)") (class "Default")
      (node (ref "D5") (pin "C") (pinfunction "C_C") (pintype "passive"))
      (node (ref "R7") (pin "2") (pinfunction "2_2") (pintype "passive"))
    )
    (net (code "55") (name "Net-(L2-Pad1)") (class "Default")
      (node (ref "L2") (pin "1") (pinfunction "1_1") (pintype "passive"))
      (node (ref "U1") (pin "M1") (pinfunction "DCDC_LP_M1") (pintype "bidirectional"))
      (node (ref "U1") (pin "M2") (pinfunction "DCDC_LP_M2") (pintype "bidirectional"))
    )
    (net (code "56") (name "Net-(Q1-G)") (class "Default")
      (node (ref "Q1") (pin "1") (pinfunction "G_1") (pintype "bidirectional"))
      (node (ref "Q2") (pin "3") (pinfunction "D_3") (pintype "bidirectional"))
      (node (ref "R2") (pin "2") (pinfunction "2_2") (pintype "passive"))
    )
    (net (code "57") (name "Net-(U1-RTC_XTALI)") (class "Default")
      (node (ref "C8") (pin "1") (pinfunction "1_1") (pintype "passive"))
      (node (ref "U1") (pin "N9") (pinfunction "RTC_XTALI_N9") (pintype "bidirectional"))
      (node (ref "Y1") (pin "P$1") (pinfunction "1_P$1") (pintype "passive"))
    )
    (net (code "58") (name "Net-(U1-RTC_XTALO)") (class "Default")
      (node (ref "C9") (pin "1") (pinfunction "1_1") (pintype "passive"))
      (node (ref "U1") (pin "P9") (pinfunction "RTC_XTALO_P9") (pintype "bidirectional"))
      (node (ref "Y1") (pin "P$2") (pinfunction "2_P$2") (pintype "passive"))
    )
    (net (code "59") (name "Net-(U1-XTALI)") (class "Default")
      (node (ref "C6") (pin "1") (pinfunction "1_1") (pintype "passive"))
      (node (ref "R4") (pin "2") (pinfunction "2_2") (pintype "passive"))
      (node (ref "U1") (pin "P11") (pinfunction "XTALI_P11") (pintype "bidirectional"))
      (node (ref "Y2") (pin "1") (pinfunction "1_1") (pintype "passive"))
    )
    (net (code "60") (name "Net-(U1-XTALO)") (class "Default")
      (node (ref "C7") (pin "1") (pinfunction "1_1") (pintype "passive"))
      (node (ref "U1") (pin "N11") (pinfunction "XTALO_N11") (pintype "bidirectional"))
      (node (ref "Y2") (pin "3") (pinfunction "2_3") (pintype "passive"))
    )
    (net (code "61") (name "Net-(U3-PTB3)") (class "Default")
      (node (ref "R7") (pin "1") (pinfunction "1_1") (pintype "passive"))
      (node (ref "U3") (pin "11") (pinfunction "PTB3_11") (pintype "bidirectional"))
    )
    (net (code "62") (name "PMIC") (class "Default")
      (node (ref "Q2") (pin "1") (pinfunction "G_1") (pintype "bidirectional"))
      (node (ref "R6") (pin "2") (pinfunction "2_2") (pintype "passive"))
      (node (ref "TP2") (pin "P$1") (pinfunction "1_P$1") (pintype "bidirectional"))
      (node (ref "U1") (pin "K7") (pinfunction "PMIC_ON_REQ_K7") (pintype "bidirectional"))
    )
    (net (code "63") (name "PORB_RESET") (class "Default")
      (node (ref "U1") (pin "M7") (pinfunction "POR_B_M7") (pintype "bidirectional"))
      (node (ref "U3") (pin "9") (pinfunction "PTB1_9") (pintype "bidirectional"))
    )
    (net (code "64") (name "PROGRAM") (class "Default")
      (node (ref "J1") (pin "11") (pinfunction "~{BOOT}_11") (pintype "bidirectional"))
      (node (ref "U3") (pin "10") (pinfunction "PTB2_10") (pintype "bidirectional"))
    )
    (net (code "65") (name "PWM0{slash}3") (class "Default")
      (node (ref "J1") (pin "32") (pinfunction "PWM0_32") (pintype "bidirectional"))
      (node (ref "U1") (pin "G5") (pinfunction "EMC_05_G5") (pintype "bidirectional"))
    )
    (net (code "66") (name "PWM1{slash}2") (class "Default")
      (node (ref "J1") (pin "47") (pinfunction "PWM1_47") (pintype "bidirectional"))
      (node (ref "U1") (pin "F2") (pinfunction "EMC_04_F2") (pintype "bidirectional"))
    )
    (net (code "67") (name "QSPI-CLK") (class "Default")
      (node (ref "U1") (pin "L4") (pinfunction "SD_B1_07_L4") (pintype "bidirectional"))
      (node (ref "U4") (pin "6") (pinfunction "CLK_6") (pintype "bidirectional"))
    )
    (net (code "68") (name "QSPI-CS") (class "Default")
      (node (ref "U1") (pin "L3") (pinfunction "SD_B1_06_L3") (pintype "bidirectional"))
      (node (ref "U4") (pin "1") (pinfunction "~{CS}_1") (pintype "bidirectional"))
    )
    (net (code "69") (name "QSPI0") (class "Default")
      (node (ref "U1") (pin "P3") (pinfunction "SD_B1_08_P3") (pintype "bidirectional"))
      (node (ref "U4") (pin "5") (pinfunction "D0/DI_5") (pintype "bidirectional"))
    )
    (net (code "70") (name "QSPI1") (class "Default")
      (node (ref "U1") (pin "N4") (pinfunction "SD_B1_09_N4") (pintype "bidirectional"))
      (node (ref "U4") (pin "2") (pinfunction "D1/DO_2") (pintype "bidirectional"))
    )
    (net (code "71") (name "QSPI2") (class "Default")
      (node (ref "U1") (pin "P4") (pinfunction "SD_B1_10_P4") (pintype "bidirectional"))
      (node (ref "U4") (pin "3") (pinfunction "D2/~{WP}_3") (pintype "bidirectional"))
    )
    (net (code "72") (name "QSPI3") (class "Default")
      (node (ref "U1") (pin "P5") (pinfunction "SD_B1_11_P5") (pintype "bidirectional"))
      (node (ref "U4") (pin "7") (pinfunction "D3/~{HOLD}_7") (pintype "bidirectional"))
    )
    (net (code "73") (name "RX0{slash}0") (class "Default")
      (node (ref "J1") (pin "19") (pinfunction "RX1_19") (pintype "bidirectional"))
      (node (ref "U1") (pin "G11") (pinfunction "AD_B0_03_G11") (pintype "bidirectional"))
    )
    (net (code "74") (name "RX1{slash}16{slash}A2") (class "Default")
      (node (ref "J1") (pin "20") (pinfunction "RX2_20") (pintype "bidirectional"))
      (node (ref "U1") (pin "K10") (pinfunction "AD_B1_07_K10") (pintype "bidirectional"))
    )
    (net (code "75") (name "SCK{slash}13") (class "Default")
      (node (ref "J1") (pin "57") (pinfunction "SPI_SCK_57") (pintype "bidirectional"))
      (node (ref "R1") (pin "2") (pinfunction "2_2") (pintype "passive"))
      (node (ref "U1") (pin "D8") (pinfunction "B0_03_D8") (pintype "bidirectional"))
    )
    (net (code "76") (name "SCL1{slash}24{slash}A10") (class "Default")
      (node (ref "J1") (pin "53") (pinfunction "I2C_SCL1_53") (pintype "bidirectional"))
      (node (ref "U1") (pin "K14") (pinfunction "AD_B0_12_K14") (pintype "bidirectional"))
    )
    (net (code "77") (name "SCL{slash}19{slash}A5") (class "Default")
      (node (ref "J1") (pin "14") (pinfunction "I2C_SCL_14") (pintype "bidirectional"))
      (node (ref "U1") (pin "J11") (pinfunction "AD_B1_00_J11") (pintype "bidirectional"))
    )
    (net (code "78") (name "SDA1{slash}25{slash}A11") (class "Default")
      (node (ref "J1") (pin "51") (pinfunction "I2C_SDA1_51") (pintype "bidirectional"))
      (node (ref "U1") (pin "L14") (pinfunction "AD_B0_13_L14") (pintype "bidirectional"))
    )
    (net (code "79") (name "SDA{slash}18{slash}A4") (class "Default")
      (node (ref "J1") (pin "12") (pinfunction "I2C_SDA_12") (pintype "bidirectional"))
      (node (ref "U1") (pin "K11") (pinfunction "AD_B1_01_K11") (pintype "bidirectional"))
    )
    (net (code "80") (name "SWD_CLK") (class "Default")
      (node (ref "TP9") (pin "P$1") (pinfunction "1_P$1") (pintype "bidirectional"))
      (node (ref "U3") (pin "14") (pinfunction "PTA0_14") (pintype "bidirectional"))
    )
    (net (code "81") (name "SWD_DIO") (class "Default")
      (node (ref "TP8") (pin "P$1") (pinfunction "1_P$1") (pintype "bidirectional"))
      (node (ref "U3") (pin "16") (pinfunction "PTA2_16") (pintype "bidirectional"))
    )
    (net (code "82") (name "TX0{slash}1") (class "Default")
      (node (ref "J1") (pin "17") (pinfunction "TX1_17") (pintype "bidirectional"))
      (node (ref "U1") (pin "M11") (pinfunction "AD_B0_02_M11") (pintype "bidirectional"))
    )
    (net (code "83") (name "TX1{slash}17{slash}A3") (class "Default")
      (node (ref "J1") (pin "22") (pinfunction "TX2_22") (pintype "bidirectional"))
      (node (ref "U1") (pin "J12") (pinfunction "AD_B1_06_J12") (pintype "bidirectional"))
    )
    (net (code "84") (name "USB2_D+") (class "Default")
      (node (ref "J1") (pin "35") (pinfunction "USBHOST_D+_35") (pintype "bidirectional"))
      (node (ref "U1") (pin "P7") (pinfunction "USB2_DP_P7") (pintype "bidirectional"))
    )
    (net (code "85") (name "USB2_D-") (class "Default")
      (node (ref "J1") (pin "37") (pinfunction "USBHOST_D-_37") (pintype "bidirectional"))
      (node (ref "U1") (pin "N7") (pinfunction "USB2_DN_N7") (pintype "bidirectional"))
    )
    (net (code "86") (name "USB_D+") (class "Default")
      (node (ref "J1") (pin "3") (pinfunction "USB_D+_3") (pintype "bidirectional"))
      (node (ref "U1") (pin "L8") (pinfunction "USB1_DP_L8") (pintype "bidirectional"))
    )
    (net (code "87") (name "USB_D-") (class "Default")
      (node (ref "J1") (pin "5") (pinfunction "USB_D-_5") (pintype "bidirectional"))
      (node (ref "U1") (pin "M8") (pinfunction "USB1_DN_M8") (pintype "bidirectional"))
    )
    (net (code "88") (name "VCC") (class "Default")
      (node (ref "C12") (pin "1") (pinfunction "1_1") (pintype "passive"))
      (node (ref "C13") (pin "1") (pinfunction "1_1") (pintype "passive"))
      (node (ref "FB1") (pin "2") (pinfunction "2_2") (pintype "passive"))
      (node (ref "TP3") (pin "P$1") (pinfunction "1_P$1") (pintype "bidirectional"))
      (node (ref "U1") (pin "N6") (pinfunction "USB1_VBUS_N6") (pintype "bidirectional"))
      (node (ref "U1") (pin "P6") (pinfunction "USB2_VBUS_P6") (pintype "bidirectional"))
    )
    (net (code "89") (name "VDD_HIGH_CAP") (class "Default")
      (node (ref "C25") (pin "1") (pinfunction "1_1") (pintype "passive"))
      (node (ref "C27") (pin "1") (pinfunction "1_1") (pintype "passive"))
      (node (ref "TP7") (pin "P$1") (pinfunction "1_P$1") (pintype "bidirectional"))
      (node (ref "U1") (pin "P8") (pinfunction "VDD_HIGH_CAP_P8") (pintype "bidirectional"))
    )
    (net (code "90") (name "VDD_SNVS_CAP") (class "Default")
      (node (ref "C23") (pin "1") (pinfunction "1_1") (pintype "passive"))
      (node (ref "TP5") (pin "P$1") (pinfunction "1_P$1") (pintype "bidirectional"))
      (node (ref "U1") (pin "M10") (pinfunction "VDD_SNVS_CAP_M10") (pintype "bidirectional"))
    )
    (net (code "91") (name "VDD_SNVS_IN") (class "Default")
      (node (ref "C22") (pin "1") (pinfunction "1_1") (pintype "passive"))
      (node (ref "D2") (pin "C") (pinfunction "C_C") (pintype "passive"))
      (node (ref "D3") (pin "C") (pinfunction "C_C") (pintype "passive"))
      (node (ref "D4") (pin "C") (pinfunction "C_C") (pintype "passive"))
      (node (ref "TP4") (pin "P$1") (pinfunction "1_P$1") (pintype "bidirectional"))
      (node (ref "U1") (pin "M9") (pinfunction "VDD_SNVS_IN_M9") (pintype "bidirectional"))
    )
    (net (code "92") (name "VDD_SOC_IN") (class "Default")
      (node (ref "C16") (pin "1") (pinfunction "1_1") (pintype "passive"))
      (node (ref "C17") (pin "1") (pinfunction "1_1") (pintype "passive"))
      (node (ref "C18") (pin "1") (pinfunction "1_1") (pintype "passive"))
      (node (ref "C19") (pin "1") (pinfunction "1_1") (pintype "passive"))
      (node (ref "L2") (pin "2") (pinfunction "2_2") (pintype "passive"))
      (node (ref "TP10") (pin "P$1") (pinfunction "1_P$1") (pintype "bidirectional"))
      (node (ref "U1") (pin "F6") (pinfunction "VDD_SOC_IN_F6") (pintype "bidirectional"))
      (node (ref "U1") (pin "F7") (pinfunction "VDD_SOC_IN_F7") (pintype "bidirectional"))
      (node (ref "U1") (pin "F8") (pinfunction "VDD_SOC_IN_F8") (pintype "bidirectional"))
      (node (ref "U1") (pin "F9") (pinfunction "VDD_SOC_IN_F9") (pintype "bidirectional"))
      (node (ref "U1") (pin "G6") (pinfunction "VDD_SOC_IN_G6") (pintype "bidirectional"))
      (node (ref "U1") (pin "G9") (pinfunction "VDD_SOC_IN_G9") (pintype "bidirectional"))
      (node (ref "U1") (pin "H6") (pinfunction "VDD_SOC_IN_H6") (pintype "bidirectional"))
      (node (ref "U1") (pin "H9") (pinfunction "VDD_SOC_IN_H9") (pintype "bidirectional"))
      (node (ref "U1") (pin "J5") (pinfunction "DCDC_SENSE_J5") (pintype "bidirectional"))
      (node (ref "U1") (pin "J9") (pinfunction "VDD_SOC_IN_J9") (pintype "bidirectional"))
    )
    (net (code "93") (name "VDD_USB_CAP") (class "Default")
      (node (ref "C20") (pin "1") (pinfunction "1_1") (pintype "passive"))
      (node (ref "C21") (pin "1") (pinfunction "1_1") (pintype "passive"))
      (node (ref "D4") (pin "A") (pinfunction "A_A") (pintype "passive"))
      (node (ref "TP11") (pin "P$1") (pinfunction "1_P$1") (pintype "bidirectional"))
      (node (ref "U1") (pin "K8") (pinfunction "VDD_USB_CAP_K8") (pintype "bidirectional"))
    )
    (net (code "94") (name "V_BATT") (class "Default")
      (node (ref "D3") (pin "A") (pinfunction "A_A") (pintype "passive"))
      (node (ref "J1") (pin "72") (pinfunction "RTC_3V_72") (pintype "bidirectional"))
    )
    (net (code "95") (name "V_USB") (class "Default")
      (node (ref "J1") (pin "9") (pinfunction "USB_VIN_9") (pintype "bidirectional"))
      (node (ref "MEAS") (pin "1") (pinfunction "1_1") (pintype "passive"))
    )
    (net (code "96") (name "unconnected-(J1-CTS1-Pad15)") (class "Default")
      (node (ref "J1") (pin "15") (pinfunction "CTS1_15") (pintype "bidirectional"))
    )
    (net (code "97") (name "unconnected-(J1-RTS1-Pad13)") (class "Default")
      (node (ref "J1") (pin "13") (pinfunction "RTS1_13") (pintype "bidirectional"))
    )
    (net (code "98") (name "unconnected-(J1-SWDCK-Pad21)") (class "Default")
      (node (ref "J1") (pin "21") (pinfunction "SWDCK_21") (pintype "bidirectional"))
    )
    (net (code "99") (name "unconnected-(J1-SWDIO-Pad23)") (class "Default")
      (node (ref "J1") (pin "23") (pinfunction "SWDIO_23") (pintype "bidirectional"))
    )
    (net (code "100") (name "unconnected-(U1-B1_02-PadC11)") (class "Default")
      (node (ref "U1") (pin "C11") (pinfunction "B1_02_C11") (pintype "bidirectional"))
    )
  )
)
